# tick-display-mk-2_1-mini.net
KiCad netlist of a schematic drawn in EAGLE
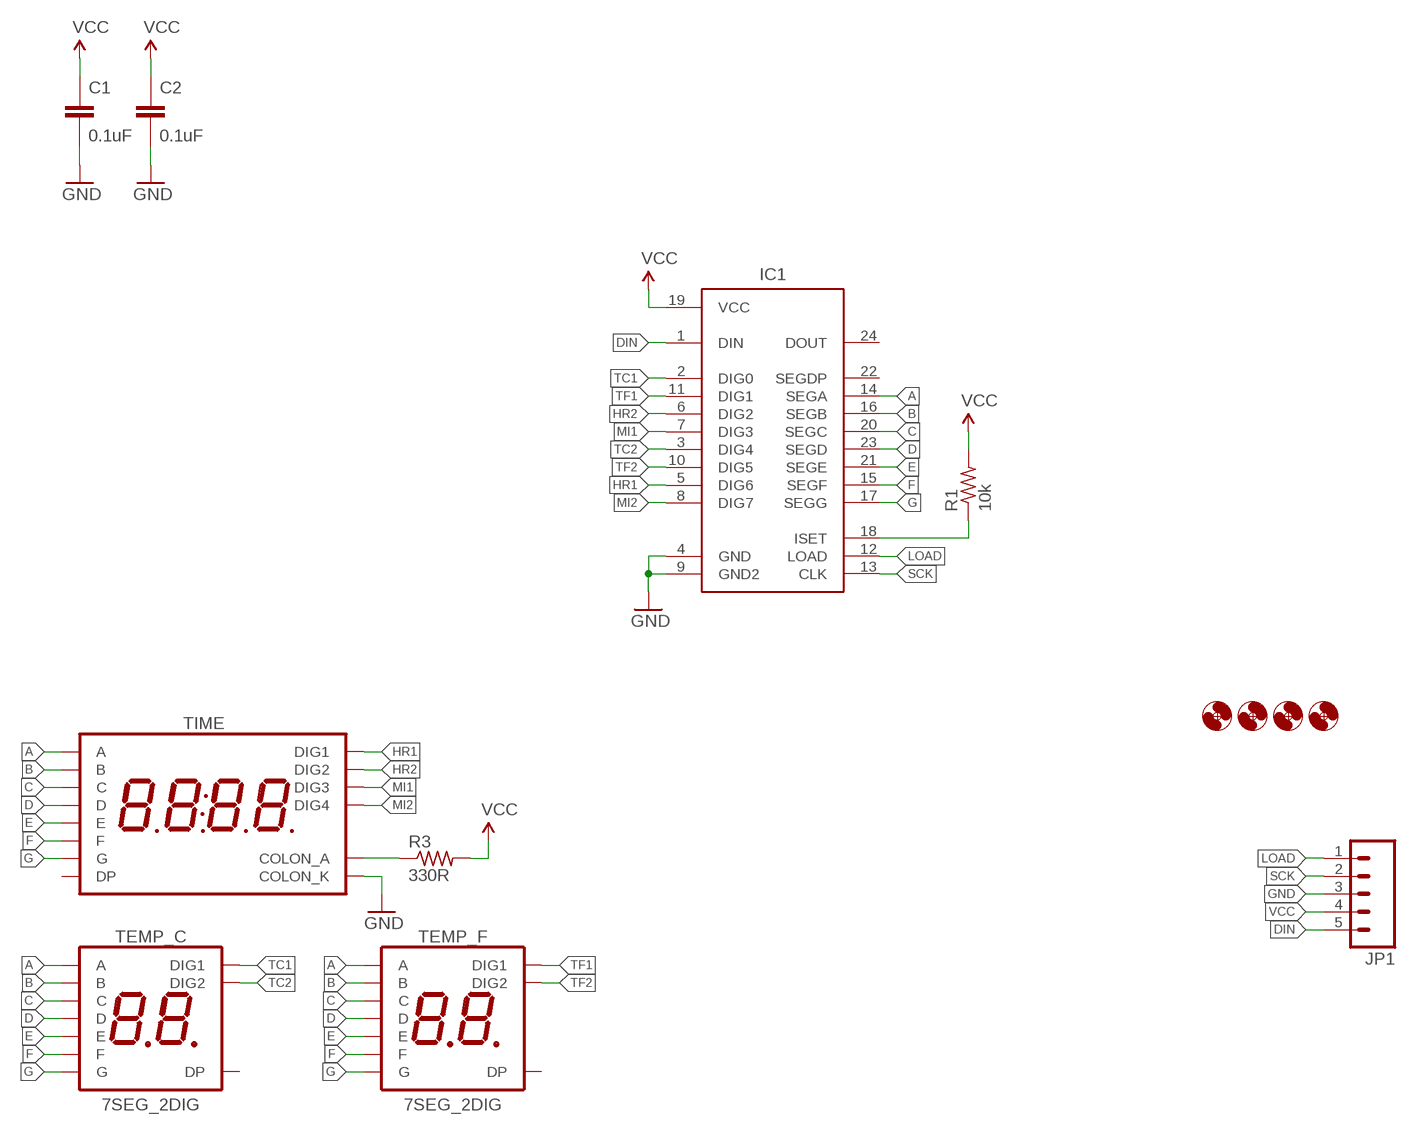
[diagram p0: schematic, sheet 1]

(export (version "E")
  (design (tool "Eeschema 10.0.6"))
  (components
    (comp (ref "C1")
      (value "0.1uF")
      (footprint "eagle-import:C025-024X044")
      (libsource (lib "eagle-import") (part "CAPACITOR-CERAMIC025-024X044"))
    )
    (comp (ref "C2")
      (value "0.1uF")
      (footprint "eagle-import:C025-024X044")
      (libsource (lib "eagle-import") (part "CAPACITOR-CERAMIC025-024X044"))
    )
    (comp (ref "H1")
      (value "HOLE#2")
      (footprint "eagle-import:HOLE-#2")
      (libsource (lib "eagle-import") (part "HOLE#2"))
    )
    (comp (ref "H2")
      (value "HOLE#2")
      (footprint "eagle-import:HOLE-#2")
      (libsource (lib "eagle-import") (part "HOLE#2"))
    )
    (comp (ref "H3")
      (value "HOLE#2")
      (footprint "eagle-import:HOLE-#2")
      (libsource (lib "eagle-import") (part "HOLE#2"))
    )
    (comp (ref "H4")
      (value "HOLE#2")
      (footprint "eagle-import:HOLE-#2")
      (libsource (lib "eagle-import") (part "HOLE#2"))
    )
    (comp (ref "IC1")
      (value "MAX7219DIP")
      (footprint "eagle-import:DIL24")
      (libsource (lib "eagle-import") (part "MAX7219DIP"))
    )
    (comp (ref "JP1")
      (value "M05JST-PH-VERT-PTH")
      (footprint "eagle-import:JST-5-PH-VERT-PTH")
      (libsource (lib "eagle-import") (part "M05JST-PH-VERT-PTH"))
    )
    (comp (ref "R1")
      (value "10k")
      (footprint "eagle-import:RESISTOR-AXIAL-PTH-5.08MM")
      (libsource (lib "eagle-import") (part "RESISTORPTH-AXIAL-5.08MM"))
    )
    (comp (ref "R3")
      (value "330R")
      (footprint "eagle-import:RESISTOR-AXIAL-PTH-5.08MM")
      (libsource (lib "eagle-import") (part "RESISTORPTH-AXIAL-5.08MM"))
    )
    (comp (ref "TEMP_C")
      (value "7SEG_2DIG")
      (footprint "eagle-import:7SEG_2DIG_14MM")
      (libsource (lib "eagle-import") (part "7SEG_2DIG"))
    )
    (comp (ref "TEMP_F")
      (value "7SEG_2DIG")
      (footprint "eagle-import:7SEG_2DIG_14MM")
      (libsource (lib "eagle-import") (part "7SEG_2DIG"))
    )
    (comp (ref "TIME")
      (value "7SED_4DIGIT_14MM14.2MM-CC")
      (footprint "eagle-import:7SEG_4DIG")
      (libsource (lib "eagle-import") (part "7SED_4DIGIT_14MM14.2MM-CC"))
    )
  )
  (nets
    (net (code "1") (name "A") (class "Default")
      (node (ref "IC1") (pin "14") (pinfunction "SEGA_14") (pintype "bidirectional"))
      (node (ref "TEMP_C") (pin "4") (pinfunction "A_4") (pintype "passive"))
      (node (ref "TEMP_F") (pin "4") (pinfunction "A_4") (pintype "passive"))
      (node (ref "TIME") (pin "P$13") (pinfunction "A_P$13") (pintype "passive"))
    )
    (net (code "2") (name "B") (class "Default")
      (node (ref "IC1") (pin "16") (pinfunction "SEGB_16") (pintype "bidirectional"))
      (node (ref "TEMP_C") (pin "3") (pinfunction "B_3") (pintype "passive"))
      (node (ref "TEMP_F") (pin "3") (pinfunction "B_3") (pintype "passive"))
      (node (ref "TIME") (pin "P$9") (pinfunction "B_P$9") (pintype "passive"))
    )
    (net (code "3") (name "C") (class "Default")
      (node (ref "IC1") (pin "20") (pinfunction "SEGC_20") (pintype "bidirectional"))
      (node (ref "TEMP_C") (pin "9") (pinfunction "C_9") (pintype "passive"))
      (node (ref "TEMP_F") (pin "9") (pinfunction "C_9") (pintype "passive"))
      (node (ref "TIME") (pin "P$4") (pinfunction "C_P$4") (pintype "passive"))
    )
    (net (code "4") (name "D") (class "Default")
      (node (ref "IC1") (pin "23") (pinfunction "SEGD_23") (pintype "bidirectional"))
      (node (ref "TEMP_C") (pin "8") (pinfunction "D_8") (pintype "passive"))
      (node (ref "TEMP_F") (pin "8") (pinfunction "D_8") (pintype "passive"))
      (node (ref "TIME") (pin "P$2") (pinfunction "D_P$2") (pintype "passive"))
    )
    (net (code "5") (name "DIN") (class "Default")
      (node (ref "IC1") (pin "1") (pinfunction "DIN_1") (pintype "bidirectional"))
      (node (ref "JP1") (pin "5") (pinfunction "5_5") (pintype "passive"))
    )
    (net (code "6") (name "E") (class "Default")
      (node (ref "IC1") (pin "21") (pinfunction "SEGE_21") (pintype "bidirectional"))
      (node (ref "TEMP_C") (pin "6") (pinfunction "E_6") (pintype "passive"))
      (node (ref "TEMP_F") (pin "6") (pinfunction "E_6") (pintype "passive"))
      (node (ref "TIME") (pin "P$1") (pinfunction "E_P$1") (pintype "passive"))
    )
    (net (code "7") (name "F") (class "Default")
      (node (ref "IC1") (pin "15") (pinfunction "SEGF_15") (pintype "bidirectional"))
      (node (ref "TEMP_C") (pin "7") (pinfunction "F_7") (pintype "passive"))
      (node (ref "TEMP_F") (pin "7") (pinfunction "F_7") (pintype "passive"))
      (node (ref "TIME") (pin "P$12") (pinfunction "F_P$12") (pintype "passive"))
    )
    (net (code "8") (name "G") (class "Default")
      (node (ref "IC1") (pin "17") (pinfunction "SEGG_17") (pintype "bidirectional"))
      (node (ref "TEMP_C") (pin "1") (pinfunction "G_1") (pintype "passive"))
      (node (ref "TEMP_F") (pin "1") (pinfunction "G_1") (pintype "passive"))
      (node (ref "TIME") (pin "P$5") (pinfunction "G_P$5") (pintype "passive"))
    )
    (net (code "9") (name "GND") (class "Default")
      (node (ref "C1") (pin "2") (pinfunction "2_2") (pintype "passive"))
      (node (ref "C2") (pin "2") (pinfunction "2_2") (pintype "passive"))
      (node (ref "IC1") (pin "4") (pinfunction "GND_4") (pintype "bidirectional"))
      (node (ref "IC1") (pin "9") (pinfunction "GND2_9") (pintype "bidirectional"))
      (node (ref "JP1") (pin "3") (pinfunction "3_3") (pintype "passive"))
      (node (ref "TIME") (pin "P$7") (pinfunction "COLON_K_P$7") (pintype "passive"))
    )
    (net (code "10") (name "HR1") (class "Default")
      (node (ref "IC1") (pin "5") (pinfunction "DIG6_5") (pintype "bidirectional"))
      (node (ref "TIME") (pin "P$14") (pinfunction "DIG1_P$14") (pintype "passive"))
    )
    (net (code "11") (name "HR2") (class "Default")
      (node (ref "IC1") (pin "6") (pinfunction "DIG2_6") (pintype "bidirectional"))
      (node (ref "TIME") (pin "P$11") (pinfunction "DIG2_P$11") (pintype "passive"))
    )
    (net (code "12") (name "LOAD") (class "Default")
      (node (ref "IC1") (pin "12") (pinfunction "LOAD_12") (pintype "bidirectional"))
      (node (ref "JP1") (pin "1") (pinfunction "1_1") (pintype "passive"))
    )
    (net (code "13") (name "MI1") (class "Default")
      (node (ref "IC1") (pin "7") (pinfunction "DIG3_7") (pintype "bidirectional"))
      (node (ref "TIME") (pin "P$10") (pinfunction "DIG3_P$10") (pintype "passive"))
    )
    (net (code "14") (name "MI2") (class "Default")
      (node (ref "IC1") (pin "8") (pinfunction "DIG7_8") (pintype "bidirectional"))
      (node (ref "TIME") (pin "P$6") (pinfunction "DIG4_P$6") (pintype "passive"))
    )
    (net (code "15") (name "Net-(IC1-ISET)") (class "Default")
      (node (ref "IC1") (pin "18") (pinfunction "ISET_18") (pintype "bidirectional"))
      (node (ref "R1") (pin "P$1") (pinfunction "1_P$1") (pintype "passive"))
    )
    (net (code "16") (name "Net-(R3-1)") (class "Default")
      (node (ref "R3") (pin "P$1") (pinfunction "1_P$1") (pintype "passive"))
      (node (ref "TIME") (pin "P$8") (pinfunction "COLON_A_P$8") (pintype "passive"))
    )
    (net (code "17") (name "SCK") (class "Default")
      (node (ref "IC1") (pin "13") (pinfunction "CLK_13") (pintype "bidirectional"))
      (node (ref "JP1") (pin "2") (pinfunction "2_2") (pintype "passive"))
    )
    (net (code "18") (name "TC1") (class "Default")
      (node (ref "IC1") (pin "2") (pinfunction "DIG0_2") (pintype "bidirectional"))
      (node (ref "TEMP_C") (pin "5") (pinfunction "DIG1_5") (pintype "passive"))
    )
    (net (code "19") (name "TC2") (class "Default")
      (node (ref "IC1") (pin "3") (pinfunction "DIG4_3") (pintype "bidirectional"))
      (node (ref "TEMP_C") (pin "10") (pinfunction "DIG2_10") (pintype "passive"))
    )
    (net (code "20") (name "TF1") (class "Default")
      (node (ref "IC1") (pin "11") (pinfunction "DIG1_11") (pintype "bidirectional"))
      (node (ref "TEMP_F") (pin "5") (pinfunction "DIG1_5") (pintype "passive"))
    )
    (net (code "21") (name "TF2") (class "Default")
      (node (ref "IC1") (pin "10") (pinfunction "DIG5_10") (pintype "bidirectional"))
      (node (ref "TEMP_F") (pin "10") (pinfunction "DIG2_10") (pintype "passive"))
    )
    (net (code "22") (name "VCC") (class "Default")
      (node (ref "C1") (pin "1") (pinfunction "1_1") (pintype "passive"))
      (node (ref "C2") (pin "1") (pinfunction "1_1") (pintype "passive"))
      (node (ref "IC1") (pin "19") (pinfunction "VCC_19") (pintype "bidirectional"))
      (node (ref "JP1") (pin "4") (pinfunction "4_4") (pintype "passive"))
      (node (ref "R1") (pin "P$2") (pinfunction "2_P$2") (pintype "passive"))
      (node (ref "R3") (pin "P$2") (pinfunction "2_P$2") (pintype "passive"))
    )
    (net (code "23") (name "unconnected-(IC1-DOUT-Pad24)") (class "Default")
      (node (ref "IC1") (pin "24") (pinfunction "DOUT_24") (pintype "bidirectional"))
    )
    (net (code "24") (name "unconnected-(IC1-SEGDP-Pad22)") (class "Default")
      (node (ref "IC1") (pin "22") (pinfunction "SEGDP_22") (pintype "bidirectional"))
    )
    (net (code "25") (name "unconnected-(TEMP_C-DP-Pad2)") (class "Default")
      (node (ref "TEMP_C") (pin "2") (pinfunction "DP_2") (pintype "passive"))
    )
    (net (code "26") (name "unconnected-(TEMP_F-DP-Pad2)") (class "Default")
      (node (ref "TEMP_F") (pin "2") (pinfunction "DP_2") (pintype "passive"))
    )
    (net (code "27") (name "unconnected-(TIME-DP-PadP$3)") (class "Default")
      (node (ref "TIME") (pin "P$3") (pinfunction "DP_P$3") (pintype "passive"))
    )
  )
)
